# Adafruit_CP2105_Friend.net
KiCad netlist of a schematic drawn in EAGLE
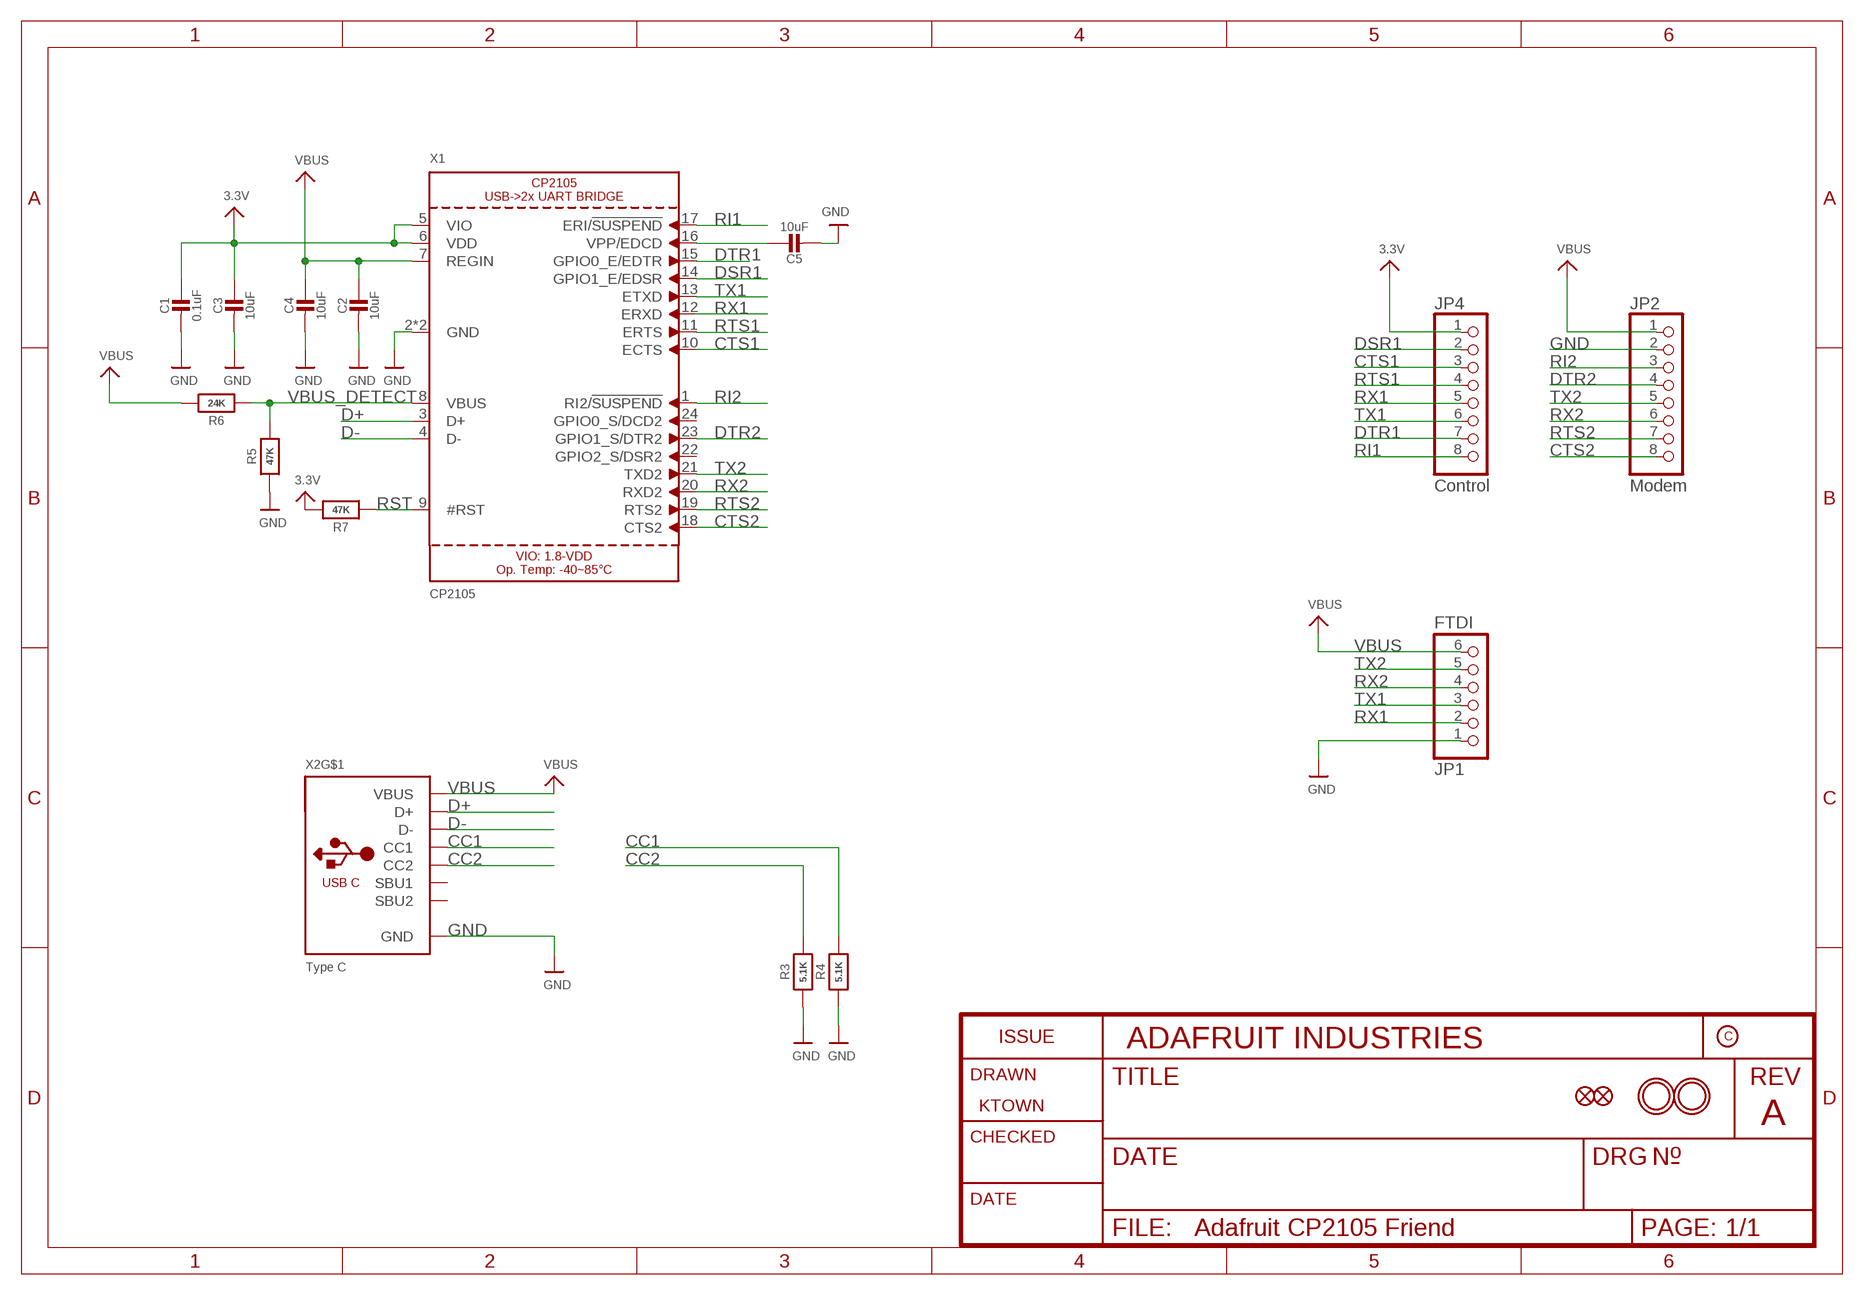
[diagram p0: schematic, sheet 1]

(export (version "E")
  (design (tool "Eeschema 10.0.6"))
  (components
    (comp (ref "C1")
      (value "0.1uF")
      (footprint "eagle-import:0603-NO")
      (libsource (lib "eagle-import") (part "CAP_CERAMIC0603_NO"))
    )
    (comp (ref "C2")
      (value "10uF")
      (footprint "eagle-import:0805-NO")
      (libsource (lib "eagle-import") (part "CAP_CERAMIC0805-NOOUTLINE"))
    )
    (comp (ref "C3")
      (value "10uF")
      (footprint "eagle-import:0805-NO")
      (libsource (lib "eagle-import") (part "CAP_CERAMIC0805-NOOUTLINE"))
    )
    (comp (ref "C4")
      (value "10uF")
      (footprint "eagle-import:0805-NO")
      (libsource (lib "eagle-import") (part "CAP_CERAMIC0805-NOOUTLINE"))
    )
    (comp (ref "C5")
      (value "10uF")
      (footprint "eagle-import:0805-NO")
      (libsource (lib "eagle-import") (part "CAP_CERAMIC0805-NOOUTLINE"))
    )
    (comp (ref "FID1")
      (value "FIDUCIAL_0.5MM")
      (footprint "eagle-import:FIDUCIAL_0.5MM")
      (libsource (lib "eagle-import") (part "FIDUCIAL_0.5MM"))
    )
    (comp (ref "FID2")
      (value "FIDUCIAL_0.5MM")
      (footprint "eagle-import:FIDUCIAL_0.5MM")
      (libsource (lib "eagle-import") (part "FIDUCIAL_0.5MM"))
    )
    (comp (ref "JP1")
      (value "FTDI")
      (footprint "eagle-import:1X06_ROUND_70")
      (libsource (lib "eagle-import") (part "HEADER-1X670MIL"))
    )
    (comp (ref "JP2")
      (value "Modem")
      (footprint "eagle-import:1X08_ROUND_70")
      (libsource (lib "eagle-import") (part "HEADER-1X870MIL"))
    )
    (comp (ref "JP4")
      (value "Control")
      (footprint "eagle-import:1X08_ROUND_70")
      (libsource (lib "eagle-import") (part "HEADER-1X870MIL"))
    )
    (comp (ref "R3")
      (value "5.1K")
      (footprint "eagle-import:0603-NO")
      (libsource (lib "eagle-import") (part "RESISTOR_0603_NOOUT"))
    )
    (comp (ref "R4")
      (value "5.1K")
      (footprint "eagle-import:0603-NO")
      (libsource (lib "eagle-import") (part "RESISTOR_0603_NOOUT"))
    )
    (comp (ref "R5")
      (value "47K")
      (footprint "eagle-import:0603-NO")
      (libsource (lib "eagle-import") (part "RESISTOR_0603_NOOUT"))
    )
    (comp (ref "R6")
      (value "24K")
      (footprint "eagle-import:0603-NO")
      (libsource (lib "eagle-import") (part "RESISTOR_0603_NOOUT"))
    )
    (comp (ref "R7")
      (value "47K")
      (footprint "eagle-import:0603-NO")
      (libsource (lib "eagle-import") (part "RESISTOR_0603_NOOUT"))
    )
    (comp (ref "U$18")
      (value "MOUNTINGHOLE2.0")
      (footprint "eagle-import:MOUNTINGHOLE_2.0_PLATED")
      (libsource (lib "eagle-import") (part "MOUNTINGHOLE2.0"))
    )
    (comp (ref "U$19")
      (value "MOUNTINGHOLE2.0")
      (footprint "eagle-import:MOUNTINGHOLE_2.0_PLATED")
      (libsource (lib "eagle-import") (part "MOUNTINGHOLE2.0"))
    )
    (comp (ref "X1")
      (value "CP2105")
      (footprint "eagle-import:QFN24_4MM")
      (libsource (lib "eagle-import") (part "CP2105"))
    )
    (comp (ref "X2")
      (value "Type C")
      (footprint "eagle-import:USB_C_CUSB31-CFM2AX-01-X")
      (libsource (lib "eagle-import") (part "USB_C"))
    )
  )
  (nets
    (net (code "1") (name "/CC1") (class "Default")
      (node (ref "R4") (pin "2") (pinfunction "2_2") (pintype "passive"))
      (node (ref "X2") (pin "A5") (pinfunction "CC1_A5") (pintype "bidirectional"))
    )
    (net (code "2") (name "/CC2") (class "Default")
      (node (ref "R3") (pin "2") (pinfunction "2_2") (pintype "passive"))
      (node (ref "X2") (pin "B5") (pinfunction "CC2_B5") (pintype "bidirectional"))
    )
    (net (code "3") (name "/CTS1") (class "Default")
      (node (ref "JP4") (pin "3") (pinfunction "3_3") (pintype "passive"))
      (node (ref "X1") (pin "10") (pinfunction "ECTS_10") (pintype "input"))
    )
    (net (code "4") (name "/CTS2") (class "Default")
      (node (ref "JP2") (pin "8") (pinfunction "8_8") (pintype "passive"))
      (node (ref "X1") (pin "18") (pinfunction "CTS2_18") (pintype "input"))
    )
    (net (code "5") (name "/D+") (class "Default")
      (node (ref "X1") (pin "3") (pinfunction "D+_3") (pintype "bidirectional"))
      (node (ref "X2") (pin "A6") (pinfunction "D+_A6") (pintype "bidirectional"))
      (node (ref "X2") (pin "B6") (pinfunction "D+_B6") (pintype "bidirectional"))
    )
    (net (code "6") (name "/D-") (class "Default")
      (node (ref "X1") (pin "4") (pinfunction "D-_4") (pintype "bidirectional"))
      (node (ref "X2") (pin "A7") (pinfunction "D-_A7") (pintype "bidirectional"))
      (node (ref "X2") (pin "B7") (pinfunction "D-_B7") (pintype "bidirectional"))
    )
    (net (code "7") (name "/DSR1") (class "Default")
      (node (ref "JP4") (pin "2") (pinfunction "2_2") (pintype "passive"))
      (node (ref "X1") (pin "14") (pinfunction "GPIO1_E/EDSR_14") (pintype "input"))
    )
    (net (code "8") (name "/DTR1") (class "Default")
      (node (ref "JP4") (pin "7") (pinfunction "7_7") (pintype "passive"))
      (node (ref "X1") (pin "15") (pinfunction "GPIO0_E/EDTR_15") (pintype "output"))
    )
    (net (code "9") (name "/DTR2") (class "Default")
      (node (ref "JP2") (pin "4") (pinfunction "4_4") (pintype "passive"))
      (node (ref "X1") (pin "23") (pinfunction "GPIO1_S/DTR2_23") (pintype "output"))
    )
    (net (code "10") (name "/RI1") (class "Default")
      (node (ref "JP4") (pin "8") (pinfunction "8_8") (pintype "passive"))
      (node (ref "X1") (pin "17") (pinfunction "ERI/~{SUSPEND}_17") (pintype "input"))
    )
    (net (code "11") (name "/RI2") (class "Default")
      (node (ref "JP2") (pin "3") (pinfunction "3_3") (pintype "passive"))
      (node (ref "X1") (pin "1") (pinfunction "RI2/~{SUSPEND}_1") (pintype "input"))
    )
    (net (code "12") (name "/RST") (class "Default")
      (node (ref "R7") (pin "1") (pinfunction "1_1") (pintype "passive"))
      (node (ref "X1") (pin "9") (pinfunction "#RST_9") (pintype "bidirectional"))
    )
    (net (code "13") (name "/RTS1") (class "Default")
      (node (ref "JP4") (pin "4") (pinfunction "4_4") (pintype "passive"))
      (node (ref "X1") (pin "11") (pinfunction "ERTS_11") (pintype "output"))
    )
    (net (code "14") (name "/RTS2") (class "Default")
      (node (ref "JP2") (pin "7") (pinfunction "7_7") (pintype "passive"))
      (node (ref "X1") (pin "19") (pinfunction "RTS2_19") (pintype "output"))
    )
    (net (code "15") (name "/RX1") (class "Default")
      (node (ref "JP1") (pin "2") (pinfunction "2_2") (pintype "passive"))
      (node (ref "JP4") (pin "5") (pinfunction "5_5") (pintype "passive"))
      (node (ref "X1") (pin "12") (pinfunction "ERXD_12") (pintype "input"))
    )
    (net (code "16") (name "/RX2") (class "Default")
      (node (ref "JP1") (pin "4") (pinfunction "4_4") (pintype "passive"))
      (node (ref "JP2") (pin "6") (pinfunction "6_6") (pintype "passive"))
      (node (ref "X1") (pin "20") (pinfunction "RXD2_20") (pintype "input"))
    )
    (net (code "17") (name "/TX1") (class "Default")
      (node (ref "JP1") (pin "3") (pinfunction "3_3") (pintype "passive"))
      (node (ref "JP4") (pin "6") (pinfunction "6_6") (pintype "passive"))
      (node (ref "X1") (pin "13") (pinfunction "ETXD_13") (pintype "output"))
    )
    (net (code "18") (name "/TX2") (class "Default")
      (node (ref "JP1") (pin "5") (pinfunction "5_5") (pintype "passive"))
      (node (ref "JP2") (pin "5") (pinfunction "5_5") (pintype "passive"))
      (node (ref "X1") (pin "21") (pinfunction "TXD2_21") (pintype "output"))
    )
    (net (code "19") (name "/VBUS_DETECT") (class "Default")
      (node (ref "R5") (pin "2") (pinfunction "2_2") (pintype "passive"))
      (node (ref "R6") (pin "1") (pinfunction "1_1") (pintype "passive"))
      (node (ref "X1") (pin "8") (pinfunction "VBUS_8") (pintype "power_in"))
    )
    (net (code "20") (name "3.3V") (class "Default")
      (node (ref "C1") (pin "1") (pinfunction "1_1") (pintype "passive"))
      (node (ref "C3") (pin "1") (pinfunction "1_1") (pintype "passive"))
      (node (ref "JP4") (pin "1") (pinfunction "1_1") (pintype "passive"))
      (node (ref "R7") (pin "2") (pinfunction "2_2") (pintype "passive"))
      (node (ref "X1") (pin "5") (pinfunction "VIO_5") (pintype "power_in"))
      (node (ref "X1") (pin "6") (pinfunction "VDD_6") (pintype "power_in"))
    )
    (net (code "21") (name "GND") (class "Default")
      (node (ref "C1") (pin "2") (pinfunction "2_2") (pintype "passive"))
      (node (ref "C2") (pin "2") (pinfunction "2_2") (pintype "passive"))
      (node (ref "C3") (pin "2") (pinfunction "2_2") (pintype "passive"))
      (node (ref "C4") (pin "2") (pinfunction "2_2") (pintype "passive"))
      (node (ref "C5") (pin "2") (pinfunction "2_2") (pintype "passive"))
      (node (ref "JP1") (pin "1") (pinfunction "1_1") (pintype "passive"))
      (node (ref "JP2") (pin "2") (pinfunction "2_2") (pintype "passive"))
      (node (ref "R3") (pin "1") (pinfunction "1_1") (pintype "passive"))
      (node (ref "R4") (pin "1") (pinfunction "1_1") (pintype "passive"))
      (node (ref "R5") (pin "1") (pinfunction "1_1") (pintype "passive"))
      (node (ref "X1") (pin "2") (pinfunction "GND_2") (pintype "power_in"))
      (node (ref "X1") (pin "THERM") (pinfunction "GND_THERM") (pintype "power_in"))
      (node (ref "X2") (pin "A1B12") (pinfunction "GND_A1B12") (pintype "power_in"))
      (node (ref "X2") (pin "B1A12") (pinfunction "GND_B1A12") (pintype "power_in"))
    )
    (net (code "22") (name "Net-(X1-VPP{slash}EDCD)") (class "Default")
      (node (ref "C5") (pin "1") (pinfunction "1_1") (pintype "passive"))
      (node (ref "X1") (pin "16") (pinfunction "VPP/EDCD_16") (pintype "input"))
    )
    (net (code "23") (name "VBUS") (class "Default")
      (node (ref "C2") (pin "1") (pinfunction "1_1") (pintype "passive"))
      (node (ref "C4") (pin "1") (pinfunction "1_1") (pintype "passive"))
      (node (ref "JP1") (pin "6") (pinfunction "6_6") (pintype "passive"))
      (node (ref "JP2") (pin "1") (pinfunction "1_1") (pintype "passive"))
      (node (ref "R6") (pin "2") (pinfunction "2_2") (pintype "passive"))
      (node (ref "X1") (pin "7") (pinfunction "REGIN_7") (pintype "power_in"))
      (node (ref "X2") (pin "A4B9") (pinfunction "VBUS_A4B9") (pintype "power_in"))
      (node (ref "X2") (pin "B4A9") (pinfunction "VBUS_B4A9") (pintype "power_in"))
    )
    (net (code "24") (name "unconnected-(X1-GPIO0_S{slash}DCD2-Pad24)") (class "Default")
      (node (ref "X1") (pin "24") (pinfunction "GPIO0_S/DCD2_24") (pintype "input"))
    )
    (net (code "25") (name "unconnected-(X1-GPIO2_S{slash}DSR2-Pad22)") (class "Default")
      (node (ref "X1") (pin "22") (pinfunction "GPIO2_S/DSR2_22") (pintype "input"))
    )
    (net (code "26") (name "unconnected-(X2A-SBU1-PadA8)") (class "Default")
      (node (ref "X2") (pin "A8") (pinfunction "SBU1_A8") (pintype "bidirectional"))
    )
    (net (code "27") (name "unconnected-(X2A-SBU2-PadB8)") (class "Default")
      (node (ref "X2") (pin "B8") (pinfunction "SBU2_B8") (pintype "bidirectional"))
    )
  )
)
